# ax5243_feather.net
KiCad netlist of a schematic drawn in EAGLE
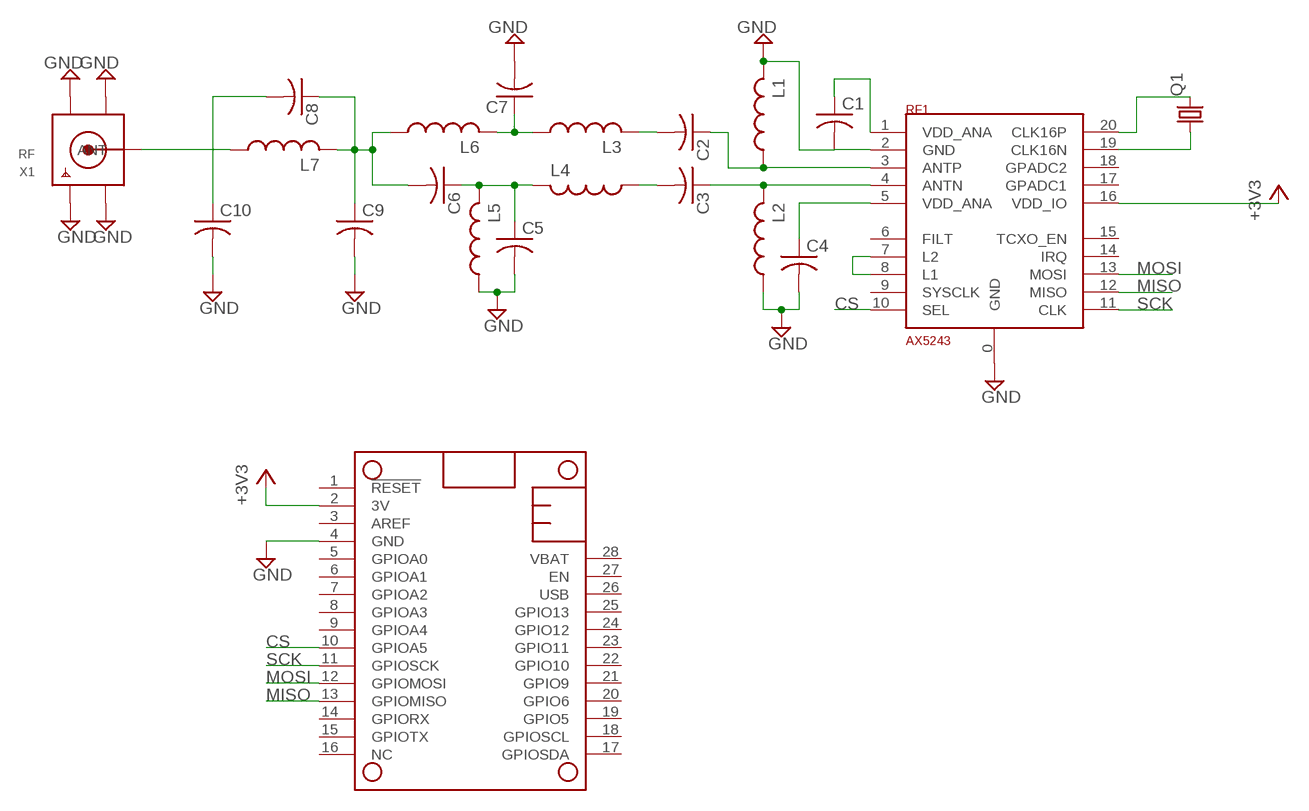
[diagram p0: schematic, sheet 1]

(export (version "E")
  (design (tool "Eeschema 10.0.6"))
  (components
    (comp (ref "C1")
      (value "C-USC0805K")
      (footprint "eagle-import:C0805K")
      (libsource (lib "eagle-import") (part "C-USC0805K"))
    )
    (comp (ref "C2")
      (value "C-USC0805K")
      (footprint "eagle-import:C0805K")
      (libsource (lib "eagle-import") (part "C-USC0805K"))
    )
    (comp (ref "C3")
      (value "C-USC0805K")
      (footprint "eagle-import:C0805K")
      (libsource (lib "eagle-import") (part "C-USC0805K"))
    )
    (comp (ref "C4")
      (value "C-USC0805K")
      (footprint "eagle-import:C0805K")
      (libsource (lib "eagle-import") (part "C-USC0805K"))
    )
    (comp (ref "C5")
      (value "C-USC0805K")
      (footprint "eagle-import:C0805K")
      (libsource (lib "eagle-import") (part "C-USC0805K"))
    )
    (comp (ref "C6")
      (value "C-USC0805K")
      (footprint "eagle-import:C0805K")
      (libsource (lib "eagle-import") (part "C-USC0805K"))
    )
    (comp (ref "C7")
      (value "C-USC0805K")
      (footprint "eagle-import:C0805K")
      (libsource (lib "eagle-import") (part "C-USC0805K"))
    )
    (comp (ref "C8")
      (value "C-USC0805K")
      (footprint "eagle-import:C0805K")
      (libsource (lib "eagle-import") (part "C-USC0805K"))
    )
    (comp (ref "C9")
      (value "C-USC0805K")
      (footprint "eagle-import:C0805K")
      (libsource (lib "eagle-import") (part "C-USC0805K"))
    )
    (comp (ref "C10")
      (value "C-USC0805K")
      (footprint "eagle-import:C0805K")
      (libsource (lib "eagle-import") (part "C-USC0805K"))
    )
    (comp (ref "L1")
      (value "L-US0805K")
      (footprint "eagle-import:C0805K")
      (libsource (lib "eagle-import") (part "L-US0805K"))
    )
    (comp (ref "L2")
      (value "L-US0805K")
      (footprint "eagle-import:C0805K")
      (libsource (lib "eagle-import") (part "L-US0805K"))
    )
    (comp (ref "L3")
      (value "L-US0805K")
      (footprint "eagle-import:C0805K")
      (libsource (lib "eagle-import") (part "L-US0805K"))
    )
    (comp (ref "L4")
      (value "L-US0805K")
      (footprint "eagle-import:C0805K")
      (libsource (lib "eagle-import") (part "L-US0805K"))
    )
    (comp (ref "L5")
      (value "L-US0805K")
      (footprint "eagle-import:C0805K")
      (libsource (lib "eagle-import") (part "L-US0805K"))
    )
    (comp (ref "L6")
      (value "L-US0805K")
      (footprint "eagle-import:C0805K")
      (libsource (lib "eagle-import") (part "L-US0805K"))
    )
    (comp (ref "L7")
      (value "L-US0805K")
      (footprint "eagle-import:C0805K")
      (libsource (lib "eagle-import") (part "L-US0805K"))
    )
    (comp (ref "MS1")
      (value "FEATHERWING")
      (footprint "eagle-import:FEATHERWING")
      (libsource (lib "eagle-import") (part "FEATHERWING"))
    )
    (comp (ref "Q1")
      (value "CRYSTALCTS406")
      (footprint "eagle-import:CTS406")
      (libsource (lib "eagle-import") (part "CRYSTALCTS406"))
    )
    (comp (ref "RF1")
      (value "AX5243")
      (footprint "eagle-import:QFN20-4X4MM")
      (libsource (lib "eagle-import") (part "AX5243"))
    )
    (comp (ref "X1")
      (value "RF")
      (footprint "eagle-import:SMA_EDGELAUNCH_UFL")
      (libsource (lib "eagle-import") (part "SMACONNECTOR_EDGE_UFL"))
    )
  )
  (nets
    (net (code "1") (name "+3V3") (class "Default")
      (node (ref "MS1") (pin "2") (pinfunction "3V_2") (pintype "power_in"))
      (node (ref "RF1") (pin "16") (pinfunction "VDD_IO_16") (pintype "bidirectional"))
    )
    (net (code "2") (name "/CS") (class "Default")
      (node (ref "MS1") (pin "10") (pinfunction "GPIOA5_10") (pintype "bidirectional"))
      (node (ref "RF1") (pin "10") (pinfunction "SEL_10") (pintype "bidirectional"))
    )
    (net (code "3") (name "/MISO") (class "Default")
      (node (ref "MS1") (pin "13") (pinfunction "GPIOMISO_13") (pintype "bidirectional"))
      (node (ref "RF1") (pin "12") (pinfunction "MISO_12") (pintype "bidirectional"))
    )
    (net (code "4") (name "/MOSI") (class "Default")
      (node (ref "MS1") (pin "12") (pinfunction "GPIOMOSI_12") (pintype "bidirectional"))
      (node (ref "RF1") (pin "13") (pinfunction "MOSI_13") (pintype "bidirectional"))
    )
    (net (code "5") (name "/SCK") (class "Default")
      (node (ref "MS1") (pin "11") (pinfunction "GPIOSCK_11") (pintype "bidirectional"))
      (node (ref "RF1") (pin "11") (pinfunction "CLK_11") (pintype "bidirectional"))
    )
    (net (code "6") (name "/USB") (class "Default")
      (node (ref "MS1") (pin "26") (pinfunction "USB_26") (pintype "power_in"))
    )
    (net (code "7") (name "/VBAT") (class "Default")
      (node (ref "MS1") (pin "28") (pinfunction "VBAT_28") (pintype "power_in"))
    )
    (net (code "8") (name "GND") (class "Default")
      (node (ref "C1") (pin "2") (pinfunction "2_2") (pintype "passive"))
      (node (ref "C10") (pin "2") (pinfunction "2_2") (pintype "passive"))
      (node (ref "C4") (pin "2") (pinfunction "2_2") (pintype "passive"))
      (node (ref "C5") (pin "2") (pinfunction "2_2") (pintype "passive"))
      (node (ref "C7") (pin "2") (pinfunction "2_2") (pintype "passive"))
      (node (ref "C9") (pin "2") (pinfunction "2_2") (pintype "passive"))
      (node (ref "L1") (pin "2") (pinfunction "2_2") (pintype "passive"))
      (node (ref "L2") (pin "1") (pinfunction "1_1") (pintype "passive"))
      (node (ref "L5") (pin "1") (pinfunction "1_1") (pintype "passive"))
      (node (ref "MS1") (pin "4") (pinfunction "GND_4") (pintype "power_in"))
      (node (ref "RF1") (pin "0") (pinfunction "GND_0") (pintype "bidirectional"))
      (node (ref "RF1") (pin "2") (pinfunction "GND_2") (pintype "bidirectional"))
      (node (ref "X1") (pin "GND@1") (pinfunction "GND1_GND@1") (pintype "power_in"))
      (node (ref "X1") (pin "GND@2") (pinfunction "GND2_GND@2") (pintype "power_in"))
      (node (ref "X1") (pin "GND@3") (pinfunction "GND3_GND@3") (pintype "power_in"))
      (node (ref "X1") (pin "GND@4") (pinfunction "GND4_GND@4") (pintype "power_in"))
    )
    (net (code "9") (name "Net-(C1-Pad1)") (class "Default")
      (node (ref "C1") (pin "1") (pinfunction "1_1") (pintype "passive"))
      (node (ref "RF1") (pin "1") (pinfunction "VDD_ANA_1") (pintype "bidirectional"))
    )
    (net (code "10") (name "Net-(C2-Pad2)") (class "Default")
      (node (ref "C2") (pin "2") (pinfunction "2_2") (pintype "passive"))
      (node (ref "L3") (pin "2") (pinfunction "2_2") (pintype "passive"))
    )
    (net (code "11") (name "Net-(C3-Pad2)") (class "Default")
      (node (ref "C3") (pin "2") (pinfunction "2_2") (pintype "passive"))
      (node (ref "L4") (pin "1") (pinfunction "1_1") (pintype "passive"))
    )
    (net (code "12") (name "Net-(C4-Pad1)") (class "Default")
      (node (ref "C4") (pin "1") (pinfunction "1_1") (pintype "passive"))
      (node (ref "RF1") (pin "5") (pinfunction "VDD_ANA_5") (pintype "bidirectional"))
    )
    (net (code "13") (name "Net-(C5-Pad1)") (class "Default")
      (node (ref "C5") (pin "1") (pinfunction "1_1") (pintype "passive"))
      (node (ref "C6") (pin "1") (pinfunction "1_1") (pintype "passive"))
      (node (ref "L4") (pin "2") (pinfunction "2_2") (pintype "passive"))
      (node (ref "L5") (pin "2") (pinfunction "2_2") (pintype "passive"))
    )
    (net (code "14") (name "Net-(C6-Pad2)") (class "Default")
      (node (ref "C6") (pin "2") (pinfunction "2_2") (pintype "passive"))
      (node (ref "C8") (pin "1") (pinfunction "1_1") (pintype "passive"))
      (node (ref "C9") (pin "1") (pinfunction "1_1") (pintype "passive"))
      (node (ref "L6") (pin "1") (pinfunction "1_1") (pintype "passive"))
      (node (ref "L7") (pin "2") (pinfunction "2_2") (pintype "passive"))
    )
    (net (code "15") (name "Net-(C7-Pad1)") (class "Default")
      (node (ref "C7") (pin "1") (pinfunction "1_1") (pintype "passive"))
      (node (ref "L3") (pin "1") (pinfunction "1_1") (pintype "passive"))
      (node (ref "L6") (pin "2") (pinfunction "2_2") (pintype "passive"))
    )
    (net (code "16") (name "Net-(Q1-2)") (class "Default")
      (node (ref "Q1") (pin "3") (pinfunction "2_3") (pintype "passive"))
      (node (ref "RF1") (pin "20") (pinfunction "CLK16P_20") (pintype "bidirectional"))
    )
    (net (code "17") (name "Net-(RF1-ANTN)") (class "Default")
      (node (ref "C3") (pin "1") (pinfunction "1_1") (pintype "passive"))
      (node (ref "L2") (pin "2") (pinfunction "2_2") (pintype "passive"))
      (node (ref "RF1") (pin "4") (pinfunction "ANTN_4") (pintype "bidirectional"))
    )
    (net (code "18") (name "Net-(RF1-ANTP)") (class "Default")
      (node (ref "C2") (pin "1") (pinfunction "1_1") (pintype "passive"))
      (node (ref "L1") (pin "1") (pinfunction "1_1") (pintype "passive"))
      (node (ref "RF1") (pin "3") (pinfunction "ANTP_3") (pintype "bidirectional"))
    )
    (net (code "19") (name "Net-(RF1-CLK16N)") (class "Default")
      (node (ref "Q1") (pin "1") (pinfunction "1_1") (pintype "passive"))
      (node (ref "RF1") (pin "19") (pinfunction "CLK16N_19") (pintype "bidirectional"))
    )
    (net (code "20") (name "Net-(RF1-L1)") (class "Default")
      (node (ref "RF1") (pin "7") (pinfunction "L2_7") (pintype "bidirectional"))
      (node (ref "RF1") (pin "8") (pinfunction "L1_8") (pintype "bidirectional"))
    )
    (net (code "21") (name "Net-(X1-ANT)") (class "Default")
      (node (ref "C10") (pin "1") (pinfunction "1_1") (pintype "passive"))
      (node (ref "C8") (pin "2") (pinfunction "2_2") (pintype "passive"))
      (node (ref "L7") (pin "1") (pinfunction "1_1") (pintype "passive"))
      (node (ref "X1") (pin "P") (pinfunction "ANT_P") (pintype "bidirectional"))
    )
    (net (code "22") (name "unconnected-(MS1-AREF-Pad3)") (class "Default")
      (node (ref "MS1") (pin "3") (pinfunction "AREF_3") (pintype "passive"))
    )
    (net (code "23") (name "unconnected-(MS1-EN-Pad27)") (class "Default")
      (node (ref "MS1") (pin "27") (pinfunction "EN_27") (pintype "passive"))
    )
    (net (code "24") (name "unconnected-(MS1-GPIO5-Pad19)") (class "Default")
      (node (ref "MS1") (pin "19") (pinfunction "GPIO5_19") (pintype "bidirectional"))
    )
    (net (code "25") (name "unconnected-(MS1-GPIO6-Pad20)") (class "Default")
      (node (ref "MS1") (pin "20") (pinfunction "GPIO6_20") (pintype "bidirectional"))
    )
    (net (code "26") (name "unconnected-(MS1-GPIO9-Pad21)") (class "Default")
      (node (ref "MS1") (pin "21") (pinfunction "GPIO9_21") (pintype "bidirectional"))
    )
    (net (code "27") (name "unconnected-(MS1-GPIO10-Pad22)") (class "Default")
      (node (ref "MS1") (pin "22") (pinfunction "GPIO10_22") (pintype "bidirectional"))
    )
    (net (code "28") (name "unconnected-(MS1-GPIO11-Pad23)") (class "Default")
      (node (ref "MS1") (pin "23") (pinfunction "GPIO11_23") (pintype "bidirectional"))
    )
    (net (code "29") (name "unconnected-(MS1-GPIO12-Pad24)") (class "Default")
      (node (ref "MS1") (pin "24") (pinfunction "GPIO12_24") (pintype "bidirectional"))
    )
    (net (code "30") (name "unconnected-(MS1-GPIO13-Pad25)") (class "Default")
      (node (ref "MS1") (pin "25") (pinfunction "GPIO13_25") (pintype "bidirectional"))
    )
    (net (code "31") (name "unconnected-(MS1-GPIOA0-Pad5)") (class "Default")
      (node (ref "MS1") (pin "5") (pinfunction "GPIOA0_5") (pintype "bidirectional"))
    )
    (net (code "32") (name "unconnected-(MS1-GPIOA1-Pad6)") (class "Default")
      (node (ref "MS1") (pin "6") (pinfunction "GPIOA1_6") (pintype "bidirectional"))
    )
    (net (code "33") (name "unconnected-(MS1-GPIOA2-Pad7)") (class "Default")
      (node (ref "MS1") (pin "7") (pinfunction "GPIOA2_7") (pintype "bidirectional"))
    )
    (net (code "34") (name "unconnected-(MS1-GPIOA3-Pad8)") (class "Default")
      (node (ref "MS1") (pin "8") (pinfunction "GPIOA3_8") (pintype "bidirectional"))
    )
    (net (code "35") (name "unconnected-(MS1-GPIOA4-Pad9)") (class "Default")
      (node (ref "MS1") (pin "9") (pinfunction "GPIOA4_9") (pintype "bidirectional"))
    )
    (net (code "36") (name "unconnected-(MS1-GPIORX-Pad14)") (class "Default")
      (node (ref "MS1") (pin "14") (pinfunction "GPIORX_14") (pintype "bidirectional"))
    )
    (net (code "37") (name "unconnected-(MS1-GPIOSCL-Pad18)") (class "Default")
      (node (ref "MS1") (pin "18") (pinfunction "GPIOSCL_18") (pintype "bidirectional"))
    )
    (net (code "38") (name "unconnected-(MS1-GPIOSDA-Pad17)") (class "Default")
      (node (ref "MS1") (pin "17") (pinfunction "GPIOSDA_17") (pintype "bidirectional"))
    )
    (net (code "39") (name "unconnected-(MS1-GPIOTX-Pad15)") (class "Default")
      (node (ref "MS1") (pin "15") (pinfunction "GPIOTX_15") (pintype "bidirectional"))
    )
    (net (code "40") (name "unconnected-(MS1-NC-Pad16)") (class "Default")
      (node (ref "MS1") (pin "16") (pinfunction "NC_16") (pintype "passive"))
    )
    (net (code "41") (name "unconnected-(MS1-~{RESET}-Pad1)") (class "Default")
      (node (ref "MS1") (pin "1") (pinfunction "~{RESET}_1") (pintype "input"))
    )
    (net (code "42") (name "unconnected-(RF1-FILT-Pad6)") (class "Default")
      (node (ref "RF1") (pin "6") (pinfunction "FILT_6") (pintype "bidirectional"))
    )
    (net (code "43") (name "unconnected-(RF1-GPADC1-Pad17)") (class "Default")
      (node (ref "RF1") (pin "17") (pinfunction "GPADC1_17") (pintype "bidirectional"))
    )
    (net (code "44") (name "unconnected-(RF1-GPADC2-Pad18)") (class "Default")
      (node (ref "RF1") (pin "18") (pinfunction "GPADC2_18") (pintype "bidirectional"))
    )
    (net (code "45") (name "unconnected-(RF1-IRQ-Pad14)") (class "Default")
      (node (ref "RF1") (pin "14") (pinfunction "IRQ_14") (pintype "bidirectional"))
    )
    (net (code "46") (name "unconnected-(RF1-SYSCLK-Pad9)") (class "Default")
      (node (ref "RF1") (pin "9") (pinfunction "SYSCLK_9") (pintype "bidirectional"))
    )
    (net (code "47") (name "unconnected-(RF1-TCXO_EN-Pad15)") (class "Default")
      (node (ref "RF1") (pin "15") (pinfunction "TCXO_EN_15") (pintype "bidirectional"))
    )
  )
)
